# Main.net
KiCad netlist of a schematic drawn in EAGLE
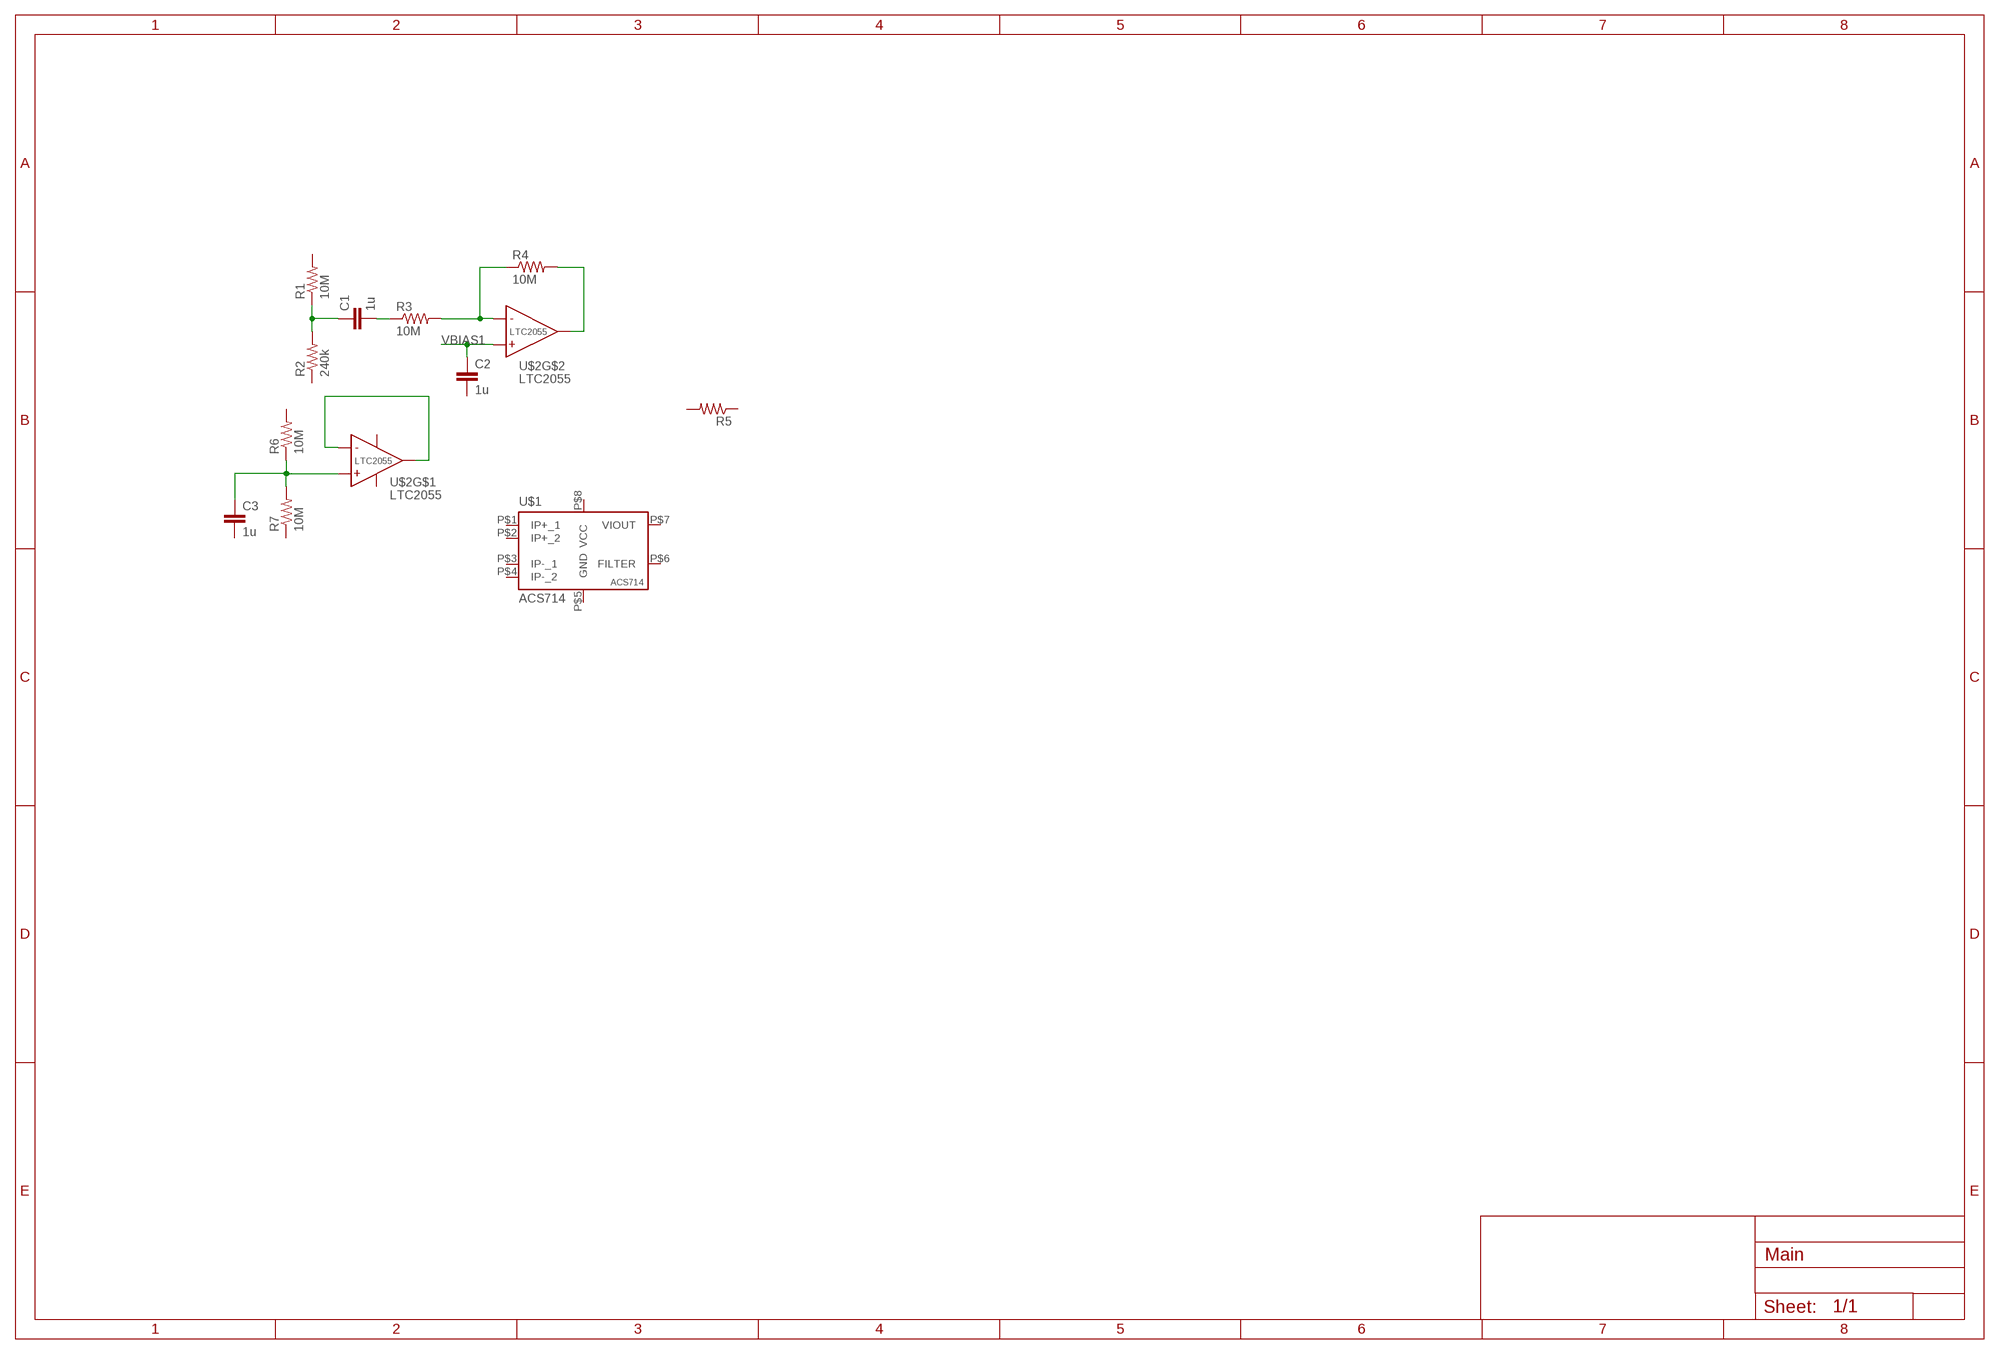
[diagram p0: schematic, sheet 1]

(export (version "E")
  (design (tool "Eeschema 10.0.6"))
  (components
    (comp (ref "C1")
      (value "1u")
      (footprint "eagle-import:C0805")
      (libsource (lib "eagle-import") (part "C-EUC0805"))
    )
    (comp (ref "C2")
      (value "1u")
      (footprint "eagle-import:C0805")
      (libsource (lib "eagle-import") (part "C-EUC0805"))
    )
    (comp (ref "C3")
      (value "1u")
      (footprint "eagle-import:C0805")
      (libsource (lib "eagle-import") (part "C-EUC0805"))
    )
    (comp (ref "R1")
      (value "10M")
      (footprint "eagle-import:R0805")
      (libsource (lib "eagle-import") (part "R-US_R0805"))
    )
    (comp (ref "R2")
      (value "240k")
      (footprint "eagle-import:R0805")
      (libsource (lib "eagle-import") (part "R-US_R0805"))
    )
    (comp (ref "R3")
      (value "10M")
      (footprint "eagle-import:R0805")
      (libsource (lib "eagle-import") (part "R-US_R0805"))
    )
    (comp (ref "R4")
      (value "10M")
      (footprint "eagle-import:R0805")
      (libsource (lib "eagle-import") (part "R-US_R0805"))
    )
    (comp (ref "R5")
      (value "R-US_R0805")
      (footprint "eagle-import:R0805")
      (libsource (lib "eagle-import") (part "R-US_R0805"))
    )
    (comp (ref "R6")
      (value "10M")
      (footprint "eagle-import:R0805")
      (libsource (lib "eagle-import") (part "R-US_R0805"))
    )
    (comp (ref "R7")
      (value "10M")
      (footprint "eagle-import:R0805")
      (libsource (lib "eagle-import") (part "R-US_R0805"))
    )
    (comp (ref "U$1")
      (value "ACS714")
      (footprint "eagle-import:8SOIC-ACS714")
      (libsource (lib "eagle-import") (part "ACS714"))
    )
    (comp (ref "U$2")
      (value "LTC2055")
      (footprint "eagle-import:MSOP8-LTC2055")
      (libsource (lib "eagle-import") (part "LTC2055"))
    )
  )
  (nets
    (net (code "1") (name "/VBIAS1") (class "Default")
      (node (ref "C2") (pin "1") (pinfunction "1_1") (pintype "passive"))
      (node (ref "U$2") (pin "P$5") (pinfunction "INP_P$5") (pintype "bidirectional"))
    )
    (net (code "2") (name "Net-(C1-Pad1)") (class "Default")
      (node (ref "C1") (pin "1") (pinfunction "1_1") (pintype "passive"))
      (node (ref "R1") (pin "1") (pinfunction "1_1") (pintype "passive"))
      (node (ref "R2") (pin "2") (pinfunction "2_2") (pintype "passive"))
    )
    (net (code "3") (name "Net-(C1-Pad2)") (class "Default")
      (node (ref "C1") (pin "2") (pinfunction "2_2") (pintype "passive"))
      (node (ref "R3") (pin "1") (pinfunction "1_1") (pintype "passive"))
    )
    (net (code "4") (name "Net-(U$2A-INM)") (class "Default")
      (node (ref "U$2") (pin "P$1") (pinfunction "OUT_P$1") (pintype "bidirectional"))
      (node (ref "U$2") (pin "P$2") (pinfunction "INM_P$2") (pintype "bidirectional"))
    )
    (net (code "5") (name "Net-(U$2A-INP)") (class "Default")
      (node (ref "C3") (pin "1") (pinfunction "1_1") (pintype "passive"))
      (node (ref "R6") (pin "1") (pinfunction "1_1") (pintype "passive"))
      (node (ref "R7") (pin "2") (pinfunction "2_2") (pintype "passive"))
      (node (ref "U$2") (pin "P$3") (pinfunction "INP_P$3") (pintype "bidirectional"))
    )
    (net (code "6") (name "Net-(U$2B-INM)") (class "Default")
      (node (ref "R3") (pin "2") (pinfunction "2_2") (pintype "passive"))
      (node (ref "R4") (pin "1") (pinfunction "1_1") (pintype "passive"))
      (node (ref "U$2") (pin "P$6") (pinfunction "INM_P$6") (pintype "bidirectional"))
    )
    (net (code "7") (name "Net-(U$2B-OUT)") (class "Default")
      (node (ref "R4") (pin "2") (pinfunction "2_2") (pintype "passive"))
      (node (ref "U$2") (pin "P$7") (pinfunction "OUT_P$7") (pintype "bidirectional"))
    )
    (net (code "8") (name "unconnected-(C2-Pad2)") (class "Default")
      (node (ref "C2") (pin "2") (pinfunction "2_2") (pintype "passive"))
    )
    (net (code "9") (name "unconnected-(C3-Pad2)") (class "Default")
      (node (ref "C3") (pin "2") (pinfunction "2_2") (pintype "passive"))
    )
    (net (code "10") (name "unconnected-(R1-Pad2)") (class "Default")
      (node (ref "R1") (pin "2") (pinfunction "2_2") (pintype "passive"))
    )
    (net (code "11") (name "unconnected-(R2-Pad1)") (class "Default")
      (node (ref "R2") (pin "1") (pinfunction "1_1") (pintype "passive"))
    )
    (net (code "12") (name "unconnected-(R5-Pad1)") (class "Default")
      (node (ref "R5") (pin "1") (pinfunction "1_1") (pintype "passive"))
    )
    (net (code "13") (name "unconnected-(R5-Pad2)") (class "Default")
      (node (ref "R5") (pin "2") (pinfunction "2_2") (pintype "passive"))
    )
    (net (code "14") (name "unconnected-(R6-Pad2)") (class "Default")
      (node (ref "R6") (pin "2") (pinfunction "2_2") (pintype "passive"))
    )
    (net (code "15") (name "unconnected-(R7-Pad1)") (class "Default")
      (node (ref "R7") (pin "1") (pinfunction "1_1") (pintype "passive"))
    )
    (net (code "16") (name "unconnected-(U$1-FILTER-PadP$6)") (class "Default")
      (node (ref "U$1") (pin "P$6") (pinfunction "FILTER_P$6") (pintype "bidirectional"))
    )
    (net (code "17") (name "unconnected-(U$1-GND-PadP$5)") (class "Default")
      (node (ref "U$1") (pin "P$5") (pinfunction "GND_P$5") (pintype "bidirectional"))
    )
    (net (code "18") (name "unconnected-(U$1-IP+_1-PadP$1)") (class "Default")
      (node (ref "U$1") (pin "P$1") (pinfunction "IP+_1_P$1") (pintype "bidirectional"))
    )
    (net (code "19") (name "unconnected-(U$1-IP+_2-PadP$2)") (class "Default")
      (node (ref "U$1") (pin "P$2") (pinfunction "IP+_2_P$2") (pintype "bidirectional"))
    )
    (net (code "20") (name "unconnected-(U$1-IP-_1-PadP$3)") (class "Default")
      (node (ref "U$1") (pin "P$3") (pinfunction "IP-_1_P$3") (pintype "bidirectional"))
    )
    (net (code "21") (name "unconnected-(U$1-IP-_2-PadP$4)") (class "Default")
      (node (ref "U$1") (pin "P$4") (pinfunction "IP-_2_P$4") (pintype "bidirectional"))
    )
    (net (code "22") (name "unconnected-(U$1-VCC-PadP$8)") (class "Default")
      (node (ref "U$1") (pin "P$8") (pinfunction "VCC_P$8") (pintype "bidirectional"))
    )
    (net (code "23") (name "unconnected-(U$1-VIOUT-PadP$7)") (class "Default")
      (node (ref "U$1") (pin "P$7") (pinfunction "VIOUT_P$7") (pintype "bidirectional"))
    )
    (net (code "24") (name "unconnected-(U$2A-VDD-PadP$8)") (class "Default")
      (node (ref "U$2") (pin "P$8") (pinfunction "VDD_P$8") (pintype "bidirectional"))
    )
    (net (code "25") (name "unconnected-(U$2A-VSS-PadP$4)") (class "Default")
      (node (ref "U$2") (pin "P$4") (pinfunction "VSS_P$4") (pintype "bidirectional"))
    )
  )
)
